# Drawdio_PNP.net
KiCad netlist of a schematic drawn in EAGLE
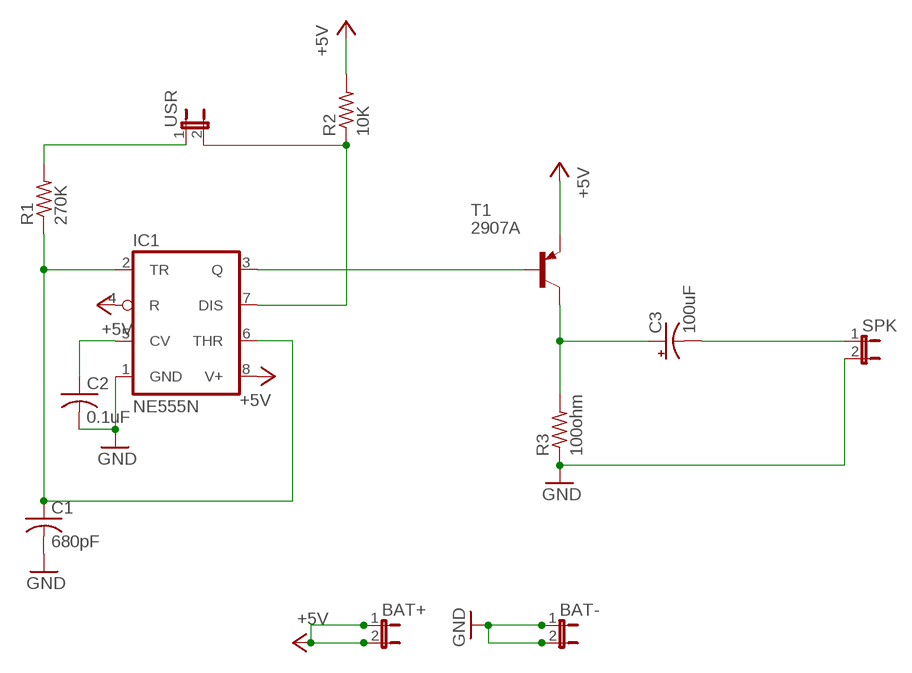
[diagram p0: schematic, sheet 1]

(export (version "E")
  (design (tool "Eeschema 10.0.6"))
  (components
    (comp (ref "BAT+")
      (value "JP1E")
      (footprint "eagle-import:JP1")
      (libsource (lib "eagle-import") (part "JP1E"))
    )
    (comp (ref "BAT-")
      (value "JP1E")
      (footprint "eagle-import:JP1")
      (libsource (lib "eagle-import") (part "JP1E"))
    )
    (comp (ref "C1")
      (value "680pF")
      (footprint "eagle-import:C025-025X050")
      (libsource (lib "eagle-import") (part "C-US025-025X050"))
    )
    (comp (ref "C2")
      (value "0.1uF")
      (footprint "eagle-import:C050-025X075")
      (libsource (lib "eagle-import") (part "C-US050-025X075"))
    )
    (comp (ref "C3")
      (value "100uF")
      (footprint "eagle-import:E2,5-5")
      (libsource (lib "eagle-import") (part "CPOL-USE2.5-5"))
    )
    (comp (ref "IC1")
      (value "NE555N")
      (footprint "eagle-import:DIL08")
      (libsource (lib "eagle-import") (part "555NNE"))
    )
    (comp (ref "R1")
      (value "270K")
      (footprint "eagle-import:0204_7")
      (libsource (lib "eagle-import") (part "R-US_0204/7"))
    )
    (comp (ref "R2")
      (value "10K")
      (footprint "eagle-import:0204_7")
      (libsource (lib "eagle-import") (part "R-US_0204/7"))
    )
    (comp (ref "R3")
      (value "100ohm")
      (footprint "eagle-import:0204_7")
      (libsource (lib "eagle-import") (part "R-US_0204/7"))
    )
    (comp (ref "SPK")
      (value "JP1E")
      (footprint "eagle-import:JP1")
      (libsource (lib "eagle-import") (part "JP1E"))
    )
    (comp (ref "T1")
      (value "2907A")
      (footprint "eagle-import:TO92-CBE")
      (libsource (lib "eagle-import") (part "-PNP-TO92-CBEMPS2907A"))
    )
    (comp (ref "USR")
      (value "JP1E")
      (footprint "eagle-import:JP1")
      (libsource (lib "eagle-import") (part "JP1E"))
    )
  )
  (nets
    (net (code "1") (name "+5V") (class "Default")
      (node (ref "BAT+") (pin "1") (pinfunction "1_1") (pintype "passive"))
      (node (ref "BAT+") (pin "2") (pinfunction "2_2") (pintype "passive"))
      (node (ref "IC1") (pin "4") (pinfunction "R_4") (pintype "input"))
      (node (ref "IC1") (pin "8") (pinfunction "V+_8") (pintype "power_in"))
      (node (ref "R2") (pin "2") (pinfunction "2_2") (pintype "passive"))
      (node (ref "T1") (pin "E") (pinfunction "E_E") (pintype "passive"))
    )
    (net (code "2") (name "GND") (class "Default")
      (node (ref "BAT-") (pin "1") (pinfunction "1_1") (pintype "passive"))
      (node (ref "BAT-") (pin "2") (pinfunction "2_2") (pintype "passive"))
      (node (ref "C1") (pin "2") (pinfunction "2_2") (pintype "passive"))
      (node (ref "C2") (pin "2") (pinfunction "2_2") (pintype "passive"))
      (node (ref "IC1") (pin "1") (pinfunction "GND_1") (pintype "power_in"))
      (node (ref "R3") (pin "1") (pinfunction "1_1") (pintype "passive"))
      (node (ref "SPK") (pin "2") (pinfunction "2_2") (pintype "passive"))
    )
    (net (code "3") (name "Net-(C3-Pad+)") (class "Default")
      (node (ref "C3") (pin "+") (pinfunction "+_+") (pintype "passive"))
      (node (ref "R3") (pin "2") (pinfunction "2_2") (pintype "passive"))
      (node (ref "T1") (pin "C") (pinfunction "C_C") (pintype "passive"))
    )
    (net (code "4") (name "Net-(C3-Pad-)") (class "Default")
      (node (ref "C3") (pin "-") (pinfunction "-_-") (pintype "passive"))
      (node (ref "SPK") (pin "1") (pinfunction "1_1") (pintype "passive"))
    )
    (net (code "5") (name "Net-(IC1-CV)") (class "Default")
      (node (ref "C2") (pin "1") (pinfunction "1_1") (pintype "passive"))
      (node (ref "IC1") (pin "5") (pinfunction "CV_5") (pintype "input"))
    )
    (net (code "6") (name "Net-(IC1-DIS)") (class "Default")
      (node (ref "IC1") (pin "7") (pinfunction "DIS_7") (pintype "input"))
      (node (ref "R2") (pin "1") (pinfunction "1_1") (pintype "passive"))
      (node (ref "USR") (pin "2") (pinfunction "2_2") (pintype "passive"))
    )
    (net (code "7") (name "Net-(IC1-Q)") (class "Default")
      (node (ref "IC1") (pin "3") (pinfunction "Q_3") (pintype "output"))
      (node (ref "T1") (pin "B") (pinfunction "B_B") (pintype "passive"))
    )
    (net (code "8") (name "Net-(IC1-THR)") (class "Default")
      (node (ref "C1") (pin "1") (pinfunction "1_1") (pintype "passive"))
      (node (ref "IC1") (pin "2") (pinfunction "TR_2") (pintype "input"))
      (node (ref "IC1") (pin "6") (pinfunction "THR_6") (pintype "input"))
      (node (ref "R1") (pin "1") (pinfunction "1_1") (pintype "passive"))
    )
    (net (code "9") (name "Net-(R1-Pad2)") (class "Default")
      (node (ref "R1") (pin "2") (pinfunction "2_2") (pintype "passive"))
      (node (ref "USR") (pin "1") (pinfunction "1_1") (pintype "passive"))
    )
  )
)
